# blocslave.net
KiCad netlist of a schematic drawn in EAGLE
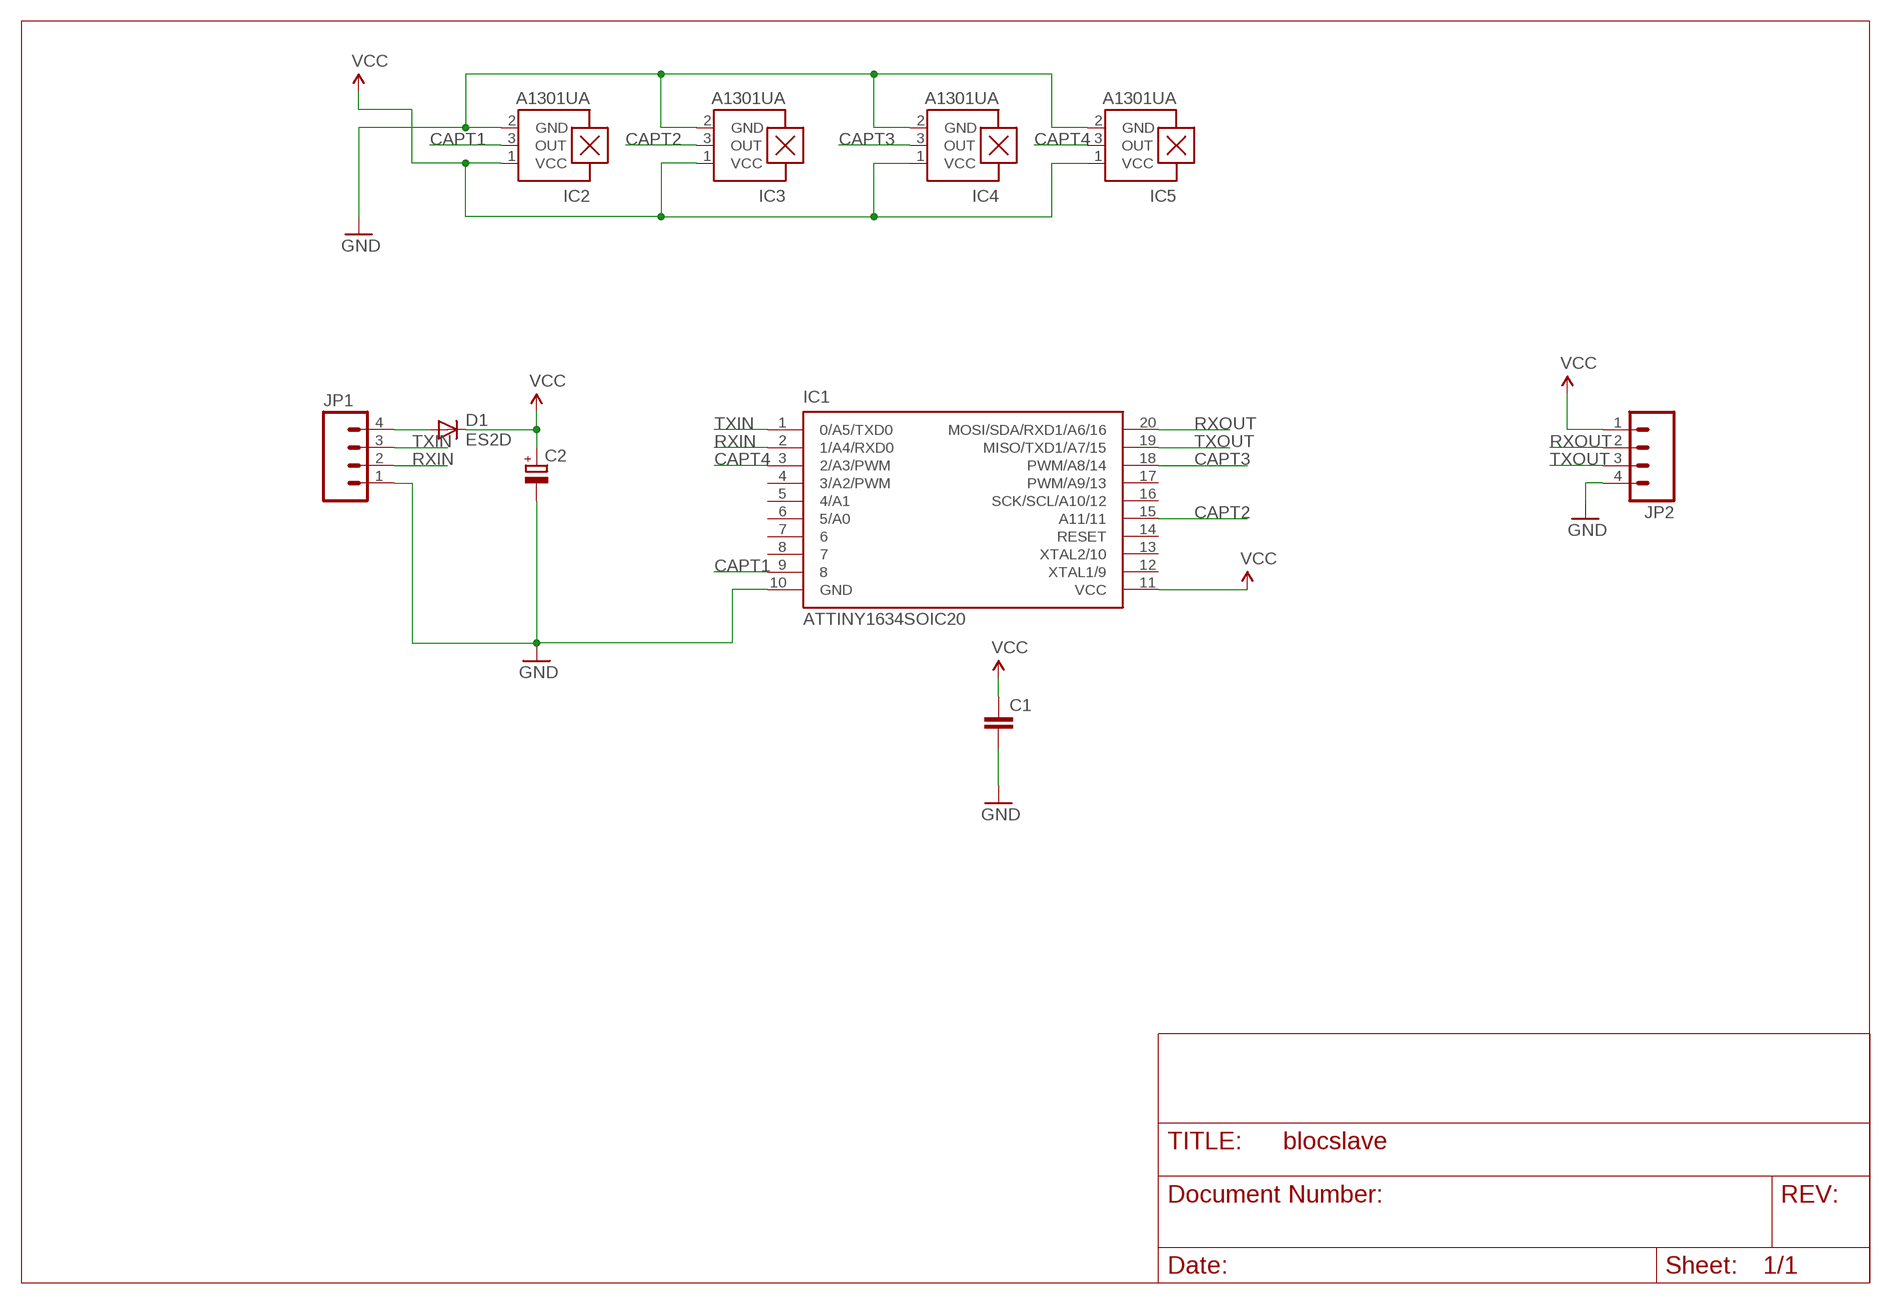
[diagram p0: schematic, sheet 1]

(export (version "E")
  (design (tool "Eeschema 10.0.6"))
  (components
    (comp (ref "C1")
      (value "C-EUC1206")
      (footprint "eagle-import:C1206")
      (libsource (lib "eagle-import") (part "C-EUC1206"))
    )
    (comp (ref "C2")
      (value "CPOL-EUSMCD")
      (footprint "eagle-import:SMC_D")
      (libsource (lib "eagle-import") (part "CPOL-EUSMCD"))
    )
    (comp (ref "D1")
      (value "ES2D")
      (footprint "eagle-import:SMB")
      (libsource (lib "eagle-import") (part "ES2D"))
    )
    (comp (ref "IC1")
      (value "ATTINY1634SOIC20")
      (footprint "eagle-import:SOIC20")
      (libsource (lib "eagle-import") (part "ATTINY1634SOIC20"))
    )
    (comp (ref "IC2")
      (value "A1301UA")
      (footprint "eagle-import:SIP3-UA")
      (fields (field (name "MF") "ALLEGRO MICROSYSTEMS, INC.") (field (name "MPN") "A1301EUA-T"))
      (libsource (lib "eagle-import") (part "A13?UA01"))
    )
    (comp (ref "IC3")
      (value "A1301UA")
      (footprint "eagle-import:SIP3-UA")
      (fields (field (name "MF") "ALLEGRO MICROSYSTEMS, INC.") (field (name "MPN") "A1301EUA-T"))
      (libsource (lib "eagle-import") (part "A13?UA01"))
    )
    (comp (ref "IC4")
      (value "A1301UA")
      (footprint "eagle-import:SIP3-UA")
      (fields (field (name "MF") "ALLEGRO MICROSYSTEMS, INC.") (field (name "MPN") "A1301EUA-T"))
      (libsource (lib "eagle-import") (part "A13?UA01"))
    )
    (comp (ref "IC5")
      (value "A1301UA")
      (footprint "eagle-import:SIP3-UA")
      (fields (field (name "MF") "ALLEGRO MICROSYSTEMS, INC.") (field (name "MPN") "A1301EUA-T"))
      (libsource (lib "eagle-import") (part "A13?UA01"))
    )
    (comp (ref "JP1")
      (value "M04")
      (footprint "eagle-import:1X04")
      (libsource (lib "eagle-import") (part "M04"))
    )
    (comp (ref "JP2")
      (value "M04")
      (footprint "eagle-import:1X04")
      (libsource (lib "eagle-import") (part "M04"))
    )
  )
  (nets
    (net (code "1") (name "/CAPT1") (class "Default")
      (node (ref "IC1") (pin "9") (pinfunction "8_9") (pintype "bidirectional"))
      (node (ref "IC2") (pin "3") (pinfunction "OUT_3") (pintype "output"))
    )
    (net (code "2") (name "/CAPT2") (class "Default")
      (node (ref "IC1") (pin "15") (pinfunction "A11/11_15") (pintype "bidirectional"))
      (node (ref "IC3") (pin "3") (pinfunction "OUT_3") (pintype "output"))
    )
    (net (code "3") (name "/CAPT3") (class "Default")
      (node (ref "IC1") (pin "18") (pinfunction "PWM/A8/14_18") (pintype "bidirectional"))
      (node (ref "IC4") (pin "3") (pinfunction "OUT_3") (pintype "output"))
    )
    (net (code "4") (name "/CAPT4") (class "Default")
      (node (ref "IC1") (pin "3") (pinfunction "2/A3/PWM_3") (pintype "bidirectional"))
      (node (ref "IC5") (pin "3") (pinfunction "OUT_3") (pintype "output"))
    )
    (net (code "5") (name "/RXIN") (class "Default")
      (node (ref "IC1") (pin "2") (pinfunction "1/A4/RXD0_2") (pintype "bidirectional"))
      (node (ref "JP1") (pin "2") (pinfunction "2_2") (pintype "passive"))
    )
    (net (code "6") (name "/RXOUT") (class "Default")
      (node (ref "IC1") (pin "20") (pinfunction "MOSI/SDA/RXD1/A6/16_20") (pintype "bidirectional"))
      (node (ref "JP2") (pin "2") (pinfunction "2_2") (pintype "passive"))
    )
    (net (code "7") (name "/TXIN") (class "Default")
      (node (ref "IC1") (pin "1") (pinfunction "0/A5/TXD0_1") (pintype "bidirectional"))
      (node (ref "JP1") (pin "3") (pinfunction "3_3") (pintype "passive"))
    )
    (net (code "8") (name "/TXOUT") (class "Default")
      (node (ref "IC1") (pin "19") (pinfunction "MISO/TXD1/A7/15_19") (pintype "bidirectional"))
      (node (ref "JP2") (pin "3") (pinfunction "3_3") (pintype "passive"))
    )
    (net (code "9") (name "GND") (class "Default")
      (node (ref "C1") (pin "2") (pinfunction "2_2") (pintype "passive"))
      (node (ref "C2") (pin "-") (pinfunction "-_-") (pintype "passive"))
      (node (ref "IC1") (pin "10") (pinfunction "GND_10") (pintype "power_in"))
      (node (ref "IC2") (pin "2") (pinfunction "GND_2") (pintype "power_in"))
      (node (ref "IC3") (pin "2") (pinfunction "GND_2") (pintype "power_in"))
      (node (ref "IC4") (pin "2") (pinfunction "GND_2") (pintype "power_in"))
      (node (ref "IC5") (pin "2") (pinfunction "GND_2") (pintype "power_in"))
      (node (ref "JP1") (pin "1") (pinfunction "1_1") (pintype "passive"))
      (node (ref "JP2") (pin "4") (pinfunction "4_4") (pintype "passive"))
    )
    (net (code "10") (name "Net-(D1-PadA)") (class "Default")
      (node (ref "D1") (pin "A") (pinfunction "A_A") (pintype "passive"))
      (node (ref "JP1") (pin "4") (pinfunction "4_4") (pintype "passive"))
    )
    (net (code "11") (name "VCC") (class "Default")
      (node (ref "C1") (pin "1") (pinfunction "1_1") (pintype "passive"))
      (node (ref "C2") (pin "+") (pinfunction "+_+") (pintype "passive"))
      (node (ref "D1") (pin "C") (pinfunction "C_C") (pintype "passive"))
      (node (ref "IC1") (pin "11") (pinfunction "VCC_11") (pintype "power_in"))
      (node (ref "IC2") (pin "1") (pinfunction "VCC_1") (pintype "power_in"))
      (node (ref "IC3") (pin "1") (pinfunction "VCC_1") (pintype "power_in"))
      (node (ref "IC4") (pin "1") (pinfunction "VCC_1") (pintype "power_in"))
      (node (ref "IC5") (pin "1") (pinfunction "VCC_1") (pintype "power_in"))
      (node (ref "JP2") (pin "1") (pinfunction "1_1") (pintype "passive"))
    )
    (net (code "12") (name "unconnected-(IC1-3{slash}A2{slash}PWM-Pad4)") (class "Default")
      (node (ref "IC1") (pin "4") (pinfunction "3/A2/PWM_4") (pintype "bidirectional"))
    )
    (net (code "13") (name "unconnected-(IC1-4{slash}A1-Pad5)") (class "Default")
      (node (ref "IC1") (pin "5") (pinfunction "4/A1_5") (pintype "bidirectional"))
    )
    (net (code "14") (name "unconnected-(IC1-5{slash}A0-Pad6)") (class "Default")
      (node (ref "IC1") (pin "6") (pinfunction "5/A0_6") (pintype "bidirectional"))
    )
    (net (code "15") (name "unconnected-(IC1-6-Pad7)") (class "Default")
      (node (ref "IC1") (pin "7") (pinfunction "6_7") (pintype "bidirectional"))
    )
    (net (code "16") (name "unconnected-(IC1-7-Pad8)") (class "Default")
      (node (ref "IC1") (pin "8") (pinfunction "7_8") (pintype "bidirectional"))
    )
    (net (code "17") (name "unconnected-(IC1-PWM{slash}A9{slash}13-Pad17)") (class "Default")
      (node (ref "IC1") (pin "17") (pinfunction "PWM/A9/13_17") (pintype "bidirectional"))
    )
    (net (code "18") (name "unconnected-(IC1-RESET-Pad14)") (class "Default")
      (node (ref "IC1") (pin "14") (pinfunction "RESET_14") (pintype "bidirectional"))
    )
    (net (code "19") (name "unconnected-(IC1-SCK{slash}SCL{slash}A10{slash}12-Pad16)") (class "Default")
      (node (ref "IC1") (pin "16") (pinfunction "SCK/SCL/A10/12_16") (pintype "bidirectional"))
    )
    (net (code "20") (name "unconnected-(IC1-XTAL1{slash}9-Pad12)") (class "Default")
      (node (ref "IC1") (pin "12") (pinfunction "XTAL1/9_12") (pintype "bidirectional"))
    )
    (net (code "21") (name "unconnected-(IC1-XTAL2{slash}10-Pad13)") (class "Default")
      (node (ref "IC1") (pin "13") (pinfunction "XTAL2/10_13") (pintype "bidirectional"))
    )
  )
)
